# main1.net
KiCad netlist of a schematic drawn in EAGLE
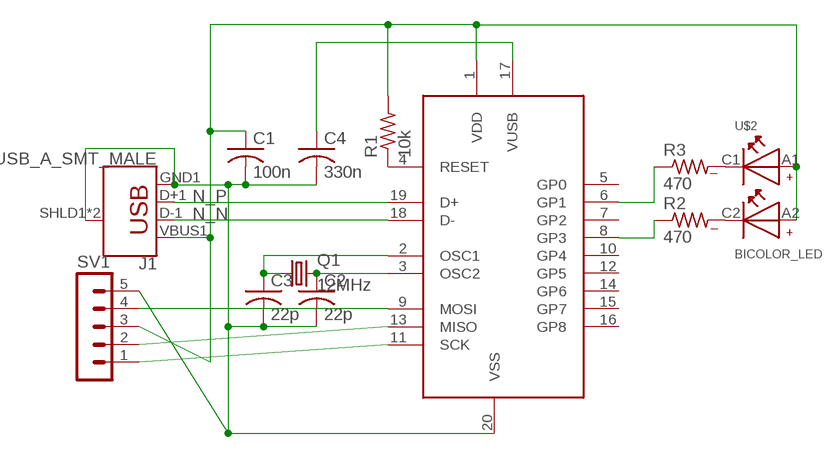
[diagram p0: schematic, sheet 1]

(export (version "E")
  (design (tool "Eeschema 10.0.6"))
  (components
    (comp (ref "C1")
      (value "100n")
      (footprint "eagle-import:C0805")
      (libsource (lib "eagle-import") (part "C-USC0805"))
    )
    (comp (ref "C2")
      (value "22p")
      (footprint "eagle-import:C0603")
      (libsource (lib "eagle-import") (part "C-USC0603"))
    )
    (comp (ref "C3")
      (value "22p")
      (footprint "eagle-import:C0603")
      (libsource (lib "eagle-import") (part "C-USC0603"))
    )
    (comp (ref "C4")
      (value "330n")
      (footprint "eagle-import:C0603")
      (libsource (lib "eagle-import") (part "C-USC0603"))
    )
    (comp (ref "J1")
      (value "USB_A_SMT_MALE")
      (footprint "eagle-import:USB-A-SMT-MALE")
      (libsource (lib "eagle-import") (part "USB_A_SMT_MALE"))
    )
    (comp (ref "Q1")
      (value "12MHz")
      (footprint "eagle-import:SM49")
      (libsource (lib "eagle-import") (part "CRYSTALSM49"))
    )
    (comp (ref "R1")
      (value "10k")
      (footprint "eagle-import:R0603")
      (libsource (lib "eagle-import") (part "R-US_R0603"))
    )
    (comp (ref "R2")
      (value "470")
      (footprint "eagle-import:R0603")
      (libsource (lib "eagle-import") (part "R-US_R0603"))
    )
    (comp (ref "R3")
      (value "470")
      (footprint "eagle-import:R0603")
      (libsource (lib "eagle-import") (part "R-US_R0603"))
    )
    (comp (ref "SV1")
      (value "MA05-1")
      (footprint "eagle-import:MA05-1")
      (libsource (lib "eagle-import") (part "MA05-1"))
    )
    (comp (ref "U$1")
      (value "MCP2210")
      (footprint "eagle-import:SOIC20_GENERIC")
      (libsource (lib "eagle-import") (part "MCP2210"))
    )
    (comp (ref "U$2")
      (value "BICOLOR_LED")
      (footprint "eagle-import:BICOLOR_LED")
      (libsource (lib "eagle-import") (part "BICOLOR_LED"))
    )
  )
  (nets
    (net (code "1") (name "/N_N") (class "Default")
      (node (ref "J1") (pin "D-1") (pinfunction "D-_D-1") (pintype "bidirectional"))
      (node (ref "U$1") (pin "18") (pinfunction "D-_18") (pintype "bidirectional"))
    )
    (net (code "2") (name "/N_P") (class "Default")
      (node (ref "J1") (pin "D+1") (pinfunction "D+_D+1") (pintype "bidirectional"))
      (node (ref "U$1") (pin "19") (pinfunction "D+_19") (pintype "bidirectional"))
    )
    (net (code "3") (name "Net-(J1-GND)") (class "Default")
      (node (ref "C1") (pin "2") (pinfunction "2_2") (pintype "passive"))
      (node (ref "C2") (pin "2") (pinfunction "2_2") (pintype "passive"))
      (node (ref "C3") (pin "2") (pinfunction "2_2") (pintype "passive"))
      (node (ref "C4") (pin "2") (pinfunction "2_2") (pintype "passive"))
      (node (ref "J1") (pin "GND1") (pinfunction "GND_GND1") (pintype "power_in"))
      (node (ref "J1") (pin "SHLD1") (pinfunction "SHIELD_SHLD1") (pintype "bidirectional"))
      (node (ref "J1") (pin "SHLD2") (pinfunction "SHIELD_SHLD2") (pintype "bidirectional"))
      (node (ref "SV1") (pin "5") (pinfunction "5_5") (pintype "passive"))
      (node (ref "U$1") (pin "20") (pinfunction "VSS_20") (pintype "bidirectional"))
    )
    (net (code "4") (name "Net-(J1-VBUS)") (class "Default")
      (node (ref "C1") (pin "1") (pinfunction "1_1") (pintype "passive"))
      (node (ref "J1") (pin "VBUS1") (pinfunction "VBUS_VBUS1") (pintype "power_in"))
      (node (ref "R1") (pin "2") (pinfunction "2_2") (pintype "passive"))
      (node (ref "SV1") (pin "3") (pinfunction "3_3") (pintype "passive"))
      (node (ref "U$1") (pin "1") (pinfunction "VDD_1") (pintype "bidirectional"))
      (node (ref "U$2") (pin "A1") (pinfunction "A1_A1") (pintype "passive"))
      (node (ref "U$2") (pin "A2") (pinfunction "A2_A2") (pintype "passive"))
    )
    (net (code "5") (name "Net-(R2-Pad2)") (class "Default")
      (node (ref "R2") (pin "2") (pinfunction "2_2") (pintype "passive"))
      (node (ref "U$2") (pin "C2") (pinfunction "C2_C2") (pintype "passive"))
    )
    (net (code "6") (name "Net-(R3-Pad2)") (class "Default")
      (node (ref "R3") (pin "2") (pinfunction "2_2") (pintype "passive"))
      (node (ref "U$2") (pin "C1") (pinfunction "C1_C1") (pintype "passive"))
    )
    (net (code "7") (name "Net-(U$1-GP1)") (class "Default")
      (node (ref "R3") (pin "1") (pinfunction "1_1") (pintype "passive"))
      (node (ref "U$1") (pin "6") (pinfunction "GP1_6") (pintype "bidirectional"))
    )
    (net (code "8") (name "Net-(U$1-GP3)") (class "Default")
      (node (ref "R2") (pin "1") (pinfunction "1_1") (pintype "passive"))
      (node (ref "U$1") (pin "8") (pinfunction "GP3_8") (pintype "bidirectional"))
    )
    (net (code "9") (name "Net-(U$1-MISO)") (class "Default")
      (node (ref "SV1") (pin "2") (pinfunction "2_2") (pintype "passive"))
      (node (ref "U$1") (pin "13") (pinfunction "MISO_13") (pintype "bidirectional"))
    )
    (net (code "10") (name "Net-(U$1-MOSI)") (class "Default")
      (node (ref "SV1") (pin "4") (pinfunction "4_4") (pintype "passive"))
      (node (ref "U$1") (pin "9") (pinfunction "MOSI_9") (pintype "bidirectional"))
    )
    (net (code "11") (name "Net-(U$1-OSC1)") (class "Default")
      (node (ref "C3") (pin "1") (pinfunction "1_1") (pintype "passive"))
      (node (ref "Q1") (pin "1") (pinfunction "1_1") (pintype "passive"))
      (node (ref "U$1") (pin "2") (pinfunction "OSC1_2") (pintype "bidirectional"))
    )
    (net (code "12") (name "Net-(U$1-OSC2)") (class "Default")
      (node (ref "C2") (pin "1") (pinfunction "1_1") (pintype "passive"))
      (node (ref "Q1") (pin "2") (pinfunction "2_2") (pintype "passive"))
      (node (ref "U$1") (pin "3") (pinfunction "OSC2_3") (pintype "bidirectional"))
    )
    (net (code "13") (name "Net-(U$1-RESET)") (class "Default")
      (node (ref "R1") (pin "1") (pinfunction "1_1") (pintype "passive"))
      (node (ref "U$1") (pin "4") (pinfunction "RESET_4") (pintype "bidirectional"))
    )
    (net (code "14") (name "Net-(U$1-SCK)") (class "Default")
      (node (ref "SV1") (pin "1") (pinfunction "1_1") (pintype "passive"))
      (node (ref "U$1") (pin "11") (pinfunction "SCK_11") (pintype "bidirectional"))
    )
    (net (code "15") (name "Net-(U$1-VUSB)") (class "Default")
      (node (ref "C4") (pin "1") (pinfunction "1_1") (pintype "passive"))
      (node (ref "U$1") (pin "17") (pinfunction "VUSB_17") (pintype "bidirectional"))
    )
    (net (code "16") (name "unconnected-(U$1-GP0-Pad5)") (class "Default")
      (node (ref "U$1") (pin "5") (pinfunction "GP0_5") (pintype "bidirectional"))
    )
    (net (code "17") (name "unconnected-(U$1-GP2-Pad7)") (class "Default")
      (node (ref "U$1") (pin "7") (pinfunction "GP2_7") (pintype "bidirectional"))
    )
    (net (code "18") (name "unconnected-(U$1-GP4-Pad10)") (class "Default")
      (node (ref "U$1") (pin "10") (pinfunction "GP4_10") (pintype "bidirectional"))
    )
    (net (code "19") (name "unconnected-(U$1-GP5-Pad12)") (class "Default")
      (node (ref "U$1") (pin "12") (pinfunction "GP5_12") (pintype "bidirectional"))
    )
    (net (code "20") (name "unconnected-(U$1-GP6-Pad14)") (class "Default")
      (node (ref "U$1") (pin "14") (pinfunction "GP6_14") (pintype "bidirectional"))
    )
    (net (code "21") (name "unconnected-(U$1-GP7-Pad15)") (class "Default")
      (node (ref "U$1") (pin "15") (pinfunction "GP7_15") (pintype "bidirectional"))
    )
    (net (code "22") (name "unconnected-(U$1-GP8-Pad16)") (class "Default")
      (node (ref "U$1") (pin "16") (pinfunction "GP8_16") (pintype "bidirectional"))
    )
  )
)
